# DC_IDE_Adapter.net
KiCad netlist of a schematic drawn in EAGLE
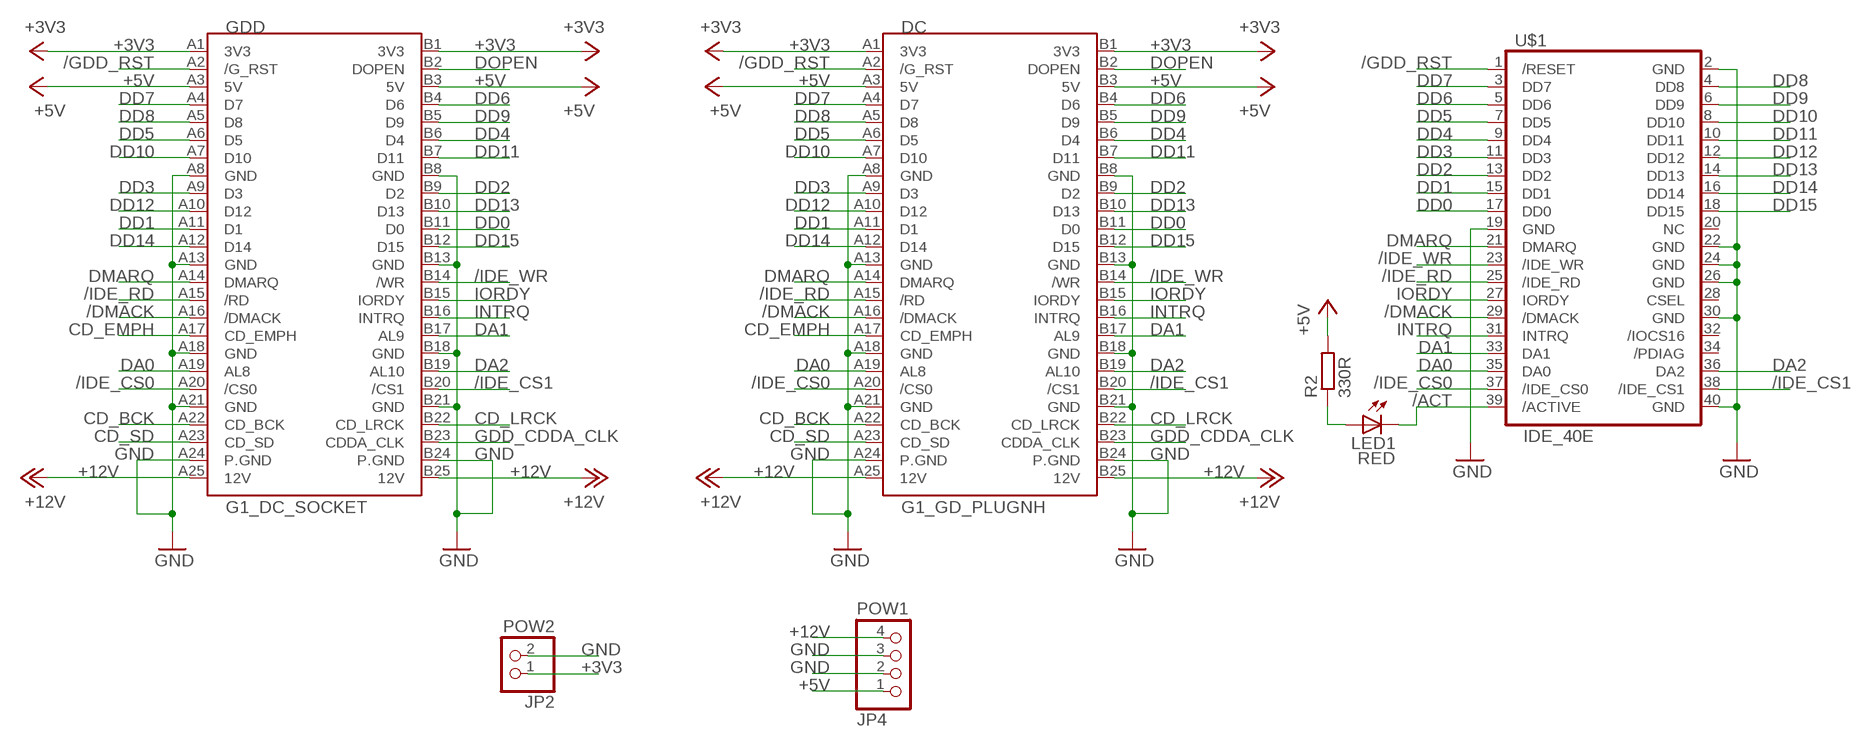
[diagram p0: schematic, sheet 1]

(export (version "E")
  (design (tool "Eeschema 10.0.6"))
  (components
    (comp (ref "DC")
      (value "G1_GD_PLUGNH")
      (footprint "eagle-import:52584-0579-NOHOLES")
      (libsource (lib "eagle-import") (part "G1_GD_PLUGNH"))
    )
    (comp (ref "GDD")
      (value "G1_DC_SOCKET")
      (footprint "eagle-import:53408-0579")
      (libsource (lib "eagle-import") (part "G1_DC_SOCKET"))
    )
    (comp (ref "JP2")
      (value "POW2")
      (footprint "eagle-import:1X02_90")
      (libsource (lib "eagle-import") (part "PINHD-1X2/90"))
    )
    (comp (ref "JP4")
      (value "POW1")
      (footprint "eagle-import:1X04_90")
      (libsource (lib "eagle-import") (part "PINHD-1X4/90"))
    )
    (comp (ref "LED1")
      (value "RED")
      (footprint "eagle-import:LED3MM")
      (libsource (lib "eagle-import") (part "LED3MM"))
    )
    (comp (ref "R2")
      (value "330R")
      (footprint "eagle-import:R0603")
      (libsource (lib "eagle-import") (part "R-EU_R0603"))
    )
    (comp (ref "U$1")
      (value "IDE_40E")
      (footprint "eagle-import:IDE_40_EDGE")
      (libsource (lib "eagle-import") (part "IDE_40E"))
    )
  )
  (nets
    (net (code "1") (name "+3V3") (class "Default")
      (node (ref "DC") (pin "A1") (pinfunction "3V3_A1") (pintype "passive"))
      (node (ref "DC") (pin "B1") (pinfunction "3V3_B1") (pintype "passive"))
      (node (ref "GDD") (pin "A1") (pinfunction "3V3_A1") (pintype "passive"))
      (node (ref "GDD") (pin "B1") (pinfunction "3V3_B1") (pintype "passive"))
      (node (ref "JP2") (pin "1") (pinfunction "1_1") (pintype "passive"))
    )
    (net (code "2") (name "+5V") (class "Default")
      (node (ref "DC") (pin "A3") (pinfunction "5V_A3") (pintype "passive"))
      (node (ref "DC") (pin "B3") (pinfunction "5V_B3") (pintype "passive"))
      (node (ref "GDD") (pin "A3") (pinfunction "5V_A3") (pintype "passive"))
      (node (ref "GDD") (pin "B3") (pinfunction "5V_B3") (pintype "passive"))
      (node (ref "JP4") (pin "1") (pinfunction "1_1") (pintype "passive"))
      (node (ref "R2") (pin "2") (pinfunction "2_2") (pintype "passive"))
    )
    (net (code "3") (name "+12V") (class "Default")
      (node (ref "DC") (pin "A25") (pinfunction "12V_A25") (pintype "passive"))
      (node (ref "DC") (pin "B25") (pinfunction "12V_B25") (pintype "passive"))
      (node (ref "GDD") (pin "A25") (pinfunction "12V_A25") (pintype "passive"))
      (node (ref "GDD") (pin "B25") (pinfunction "12V_B25") (pintype "passive"))
      (node (ref "JP4") (pin "4") (pinfunction "4_4") (pintype "passive"))
    )
    (net (code "4") (name "/CD_BCK") (class "Default")
      (node (ref "DC") (pin "A22") (pinfunction "CD_BCK_A22") (pintype "passive"))
      (node (ref "GDD") (pin "A22") (pinfunction "CD_BCK_A22") (pintype "passive"))
    )
    (net (code "5") (name "/CD_EMPH") (class "Default")
      (node (ref "DC") (pin "A17") (pinfunction "CD_EMPH_A17") (pintype "passive"))
      (node (ref "GDD") (pin "A17") (pinfunction "CD_EMPH_A17") (pintype "passive"))
    )
    (net (code "6") (name "/CD_LRCK") (class "Default")
      (node (ref "DC") (pin "B22") (pinfunction "CD_LRCK_B22") (pintype "passive"))
      (node (ref "GDD") (pin "B22") (pinfunction "CD_LRCK_B22") (pintype "passive"))
    )
    (net (code "7") (name "/CD_SD") (class "Default")
      (node (ref "DC") (pin "A23") (pinfunction "CD_SD_A23") (pintype "passive"))
      (node (ref "GDD") (pin "A23") (pinfunction "CD_SD_A23") (pintype "passive"))
    )
    (net (code "8") (name "/DA0") (class "Default")
      (node (ref "DC") (pin "A19") (pinfunction "AL8_A19") (pintype "passive"))
      (node (ref "GDD") (pin "A19") (pinfunction "AL8_A19") (pintype "passive"))
      (node (ref "U$1") (pin "35") (pinfunction "DA0_35") (pintype "input"))
    )
    (net (code "9") (name "/DA1") (class "Default")
      (node (ref "DC") (pin "B17") (pinfunction "AL9_B17") (pintype "passive"))
      (node (ref "GDD") (pin "B17") (pinfunction "AL9_B17") (pintype "passive"))
      (node (ref "U$1") (pin "33") (pinfunction "DA1_33") (pintype "input"))
    )
    (net (code "10") (name "/DA2") (class "Default")
      (node (ref "DC") (pin "B19") (pinfunction "AL10_B19") (pintype "passive"))
      (node (ref "GDD") (pin "B19") (pinfunction "AL10_B19") (pintype "passive"))
      (node (ref "U$1") (pin "36") (pinfunction "DA2_36") (pintype "input"))
    )
    (net (code "11") (name "/DD0") (class "Default")
      (node (ref "DC") (pin "B11") (pinfunction "D0_B11") (pintype "passive"))
      (node (ref "GDD") (pin "B11") (pinfunction "D0_B11") (pintype "passive"))
      (node (ref "U$1") (pin "17") (pinfunction "DD0_17") (pintype "bidirectional"))
    )
    (net (code "12") (name "/DD1") (class "Default")
      (node (ref "DC") (pin "A11") (pinfunction "D1_A11") (pintype "passive"))
      (node (ref "GDD") (pin "A11") (pinfunction "D1_A11") (pintype "passive"))
      (node (ref "U$1") (pin "15") (pinfunction "DD1_15") (pintype "bidirectional"))
    )
    (net (code "13") (name "/DD2") (class "Default")
      (node (ref "DC") (pin "B9") (pinfunction "D2_B9") (pintype "passive"))
      (node (ref "GDD") (pin "B9") (pinfunction "D2_B9") (pintype "passive"))
      (node (ref "U$1") (pin "13") (pinfunction "DD2_13") (pintype "bidirectional"))
    )
    (net (code "14") (name "/DD3") (class "Default")
      (node (ref "DC") (pin "A9") (pinfunction "D3_A9") (pintype "passive"))
      (node (ref "GDD") (pin "A9") (pinfunction "D3_A9") (pintype "passive"))
      (node (ref "U$1") (pin "11") (pinfunction "DD3_11") (pintype "bidirectional"))
    )
    (net (code "15") (name "/DD4") (class "Default")
      (node (ref "DC") (pin "B6") (pinfunction "D4_B6") (pintype "passive"))
      (node (ref "GDD") (pin "B6") (pinfunction "D4_B6") (pintype "passive"))
      (node (ref "U$1") (pin "9") (pinfunction "DD4_9") (pintype "bidirectional"))
    )
    (net (code "16") (name "/DD5") (class "Default")
      (node (ref "DC") (pin "A6") (pinfunction "D5_A6") (pintype "passive"))
      (node (ref "GDD") (pin "A6") (pinfunction "D5_A6") (pintype "passive"))
      (node (ref "U$1") (pin "7") (pinfunction "DD5_7") (pintype "bidirectional"))
    )
    (net (code "17") (name "/DD6") (class "Default")
      (node (ref "DC") (pin "B4") (pinfunction "D6_B4") (pintype "passive"))
      (node (ref "GDD") (pin "B4") (pinfunction "D6_B4") (pintype "passive"))
      (node (ref "U$1") (pin "5") (pinfunction "DD6_5") (pintype "bidirectional"))
    )
    (net (code "18") (name "/DD7") (class "Default")
      (node (ref "DC") (pin "A4") (pinfunction "D7_A4") (pintype "passive"))
      (node (ref "GDD") (pin "A4") (pinfunction "D7_A4") (pintype "passive"))
      (node (ref "U$1") (pin "3") (pinfunction "DD7_3") (pintype "bidirectional"))
    )
    (net (code "19") (name "/DD8") (class "Default")
      (node (ref "DC") (pin "A5") (pinfunction "D8_A5") (pintype "passive"))
      (node (ref "GDD") (pin "A5") (pinfunction "D8_A5") (pintype "passive"))
      (node (ref "U$1") (pin "4") (pinfunction "DD8_4") (pintype "bidirectional"))
    )
    (net (code "20") (name "/DD9") (class "Default")
      (node (ref "DC") (pin "B5") (pinfunction "D9_B5") (pintype "passive"))
      (node (ref "GDD") (pin "B5") (pinfunction "D9_B5") (pintype "passive"))
      (node (ref "U$1") (pin "6") (pinfunction "DD9_6") (pintype "bidirectional"))
    )
    (net (code "21") (name "/DD10") (class "Default")
      (node (ref "DC") (pin "A7") (pinfunction "D10_A7") (pintype "passive"))
      (node (ref "GDD") (pin "A7") (pinfunction "D10_A7") (pintype "passive"))
      (node (ref "U$1") (pin "8") (pinfunction "DD10_8") (pintype "bidirectional"))
    )
    (net (code "22") (name "/DD11") (class "Default")
      (node (ref "DC") (pin "B7") (pinfunction "D11_B7") (pintype "passive"))
      (node (ref "GDD") (pin "B7") (pinfunction "D11_B7") (pintype "passive"))
      (node (ref "U$1") (pin "10") (pinfunction "DD11_10") (pintype "bidirectional"))
    )
    (net (code "23") (name "/DD12") (class "Default")
      (node (ref "DC") (pin "A10") (pinfunction "D12_A10") (pintype "passive"))
      (node (ref "GDD") (pin "A10") (pinfunction "D12_A10") (pintype "passive"))
      (node (ref "U$1") (pin "12") (pinfunction "DD12_12") (pintype "bidirectional"))
    )
    (net (code "24") (name "/DD13") (class "Default")
      (node (ref "DC") (pin "B10") (pinfunction "D13_B10") (pintype "passive"))
      (node (ref "GDD") (pin "B10") (pinfunction "D13_B10") (pintype "passive"))
      (node (ref "U$1") (pin "14") (pinfunction "DD13_14") (pintype "bidirectional"))
    )
    (net (code "25") (name "/DD14") (class "Default")
      (node (ref "DC") (pin "A12") (pinfunction "D14_A12") (pintype "passive"))
      (node (ref "GDD") (pin "A12") (pinfunction "D14_A12") (pintype "passive"))
      (node (ref "U$1") (pin "16") (pinfunction "DD14_16") (pintype "bidirectional"))
    )
    (net (code "26") (name "/DD15") (class "Default")
      (node (ref "DC") (pin "B12") (pinfunction "D15_B12") (pintype "passive"))
      (node (ref "GDD") (pin "B12") (pinfunction "D15_B12") (pintype "passive"))
      (node (ref "U$1") (pin "18") (pinfunction "DD15_18") (pintype "bidirectional"))
    )
    (net (code "27") (name "/DMARQ") (class "Default")
      (node (ref "DC") (pin "A14") (pinfunction "DMARQ_A14") (pintype "passive"))
      (node (ref "GDD") (pin "A14") (pinfunction "DMARQ_A14") (pintype "passive"))
      (node (ref "U$1") (pin "21") (pinfunction "DMARQ_21") (pintype "output"))
    )
    (net (code "28") (name "/DOPEN") (class "Default")
      (node (ref "DC") (pin "B2") (pinfunction "DOPEN_B2") (pintype "passive"))
      (node (ref "GDD") (pin "B2") (pinfunction "DOPEN_B2") (pintype "passive"))
    )
    (net (code "29") (name "/GDD_CDDA_CLK") (class "Default")
      (node (ref "DC") (pin "B23") (pinfunction "CDDA_CLK_B23") (pintype "passive"))
      (node (ref "GDD") (pin "B23") (pinfunction "CDDA_CLK_B23") (pintype "passive"))
    )
    (net (code "30") (name "/INTRQ") (class "Default")
      (node (ref "DC") (pin "B16") (pinfunction "INTRQ_B16") (pintype "passive"))
      (node (ref "GDD") (pin "B16") (pinfunction "INTRQ_B16") (pintype "passive"))
      (node (ref "U$1") (pin "31") (pinfunction "INTRQ_31") (pintype "output"))
    )
    (net (code "31") (name "/IORDY") (class "Default")
      (node (ref "DC") (pin "B15") (pinfunction "IORDY_B15") (pintype "passive"))
      (node (ref "GDD") (pin "B15") (pinfunction "IORDY_B15") (pintype "passive"))
      (node (ref "U$1") (pin "27") (pinfunction "IORDY_27") (pintype "bidirectional"))
    )
    (net (code "32") (name "/{slash}ACT") (class "Default")
      (node (ref "LED1") (pin "K") (pinfunction "C_K") (pintype "passive"))
      (node (ref "U$1") (pin "39") (pinfunction "/ACTIVE_39") (pintype "output"))
    )
    (net (code "33") (name "/{slash}DMACK") (class "Default")
      (node (ref "DC") (pin "A16") (pinfunction "/DMACK_A16") (pintype "passive"))
      (node (ref "GDD") (pin "A16") (pinfunction "/DMACK_A16") (pintype "passive"))
      (node (ref "U$1") (pin "29") (pinfunction "/DMACK_29") (pintype "input"))
    )
    (net (code "34") (name "/{slash}GDD_RST") (class "Default")
      (node (ref "DC") (pin "A2") (pinfunction "/G_RST_A2") (pintype "passive"))
      (node (ref "GDD") (pin "A2") (pinfunction "/G_RST_A2") (pintype "passive"))
      (node (ref "U$1") (pin "1") (pinfunction "/RESET_1") (pintype "input"))
    )
    (net (code "35") (name "/{slash}IDE_CS0") (class "Default")
      (node (ref "DC") (pin "A20") (pinfunction "/CS0_A20") (pintype "passive"))
      (node (ref "GDD") (pin "A20") (pinfunction "/CS0_A20") (pintype "passive"))
      (node (ref "U$1") (pin "37") (pinfunction "/IDE_CS0_37") (pintype "input"))
    )
    (net (code "36") (name "/{slash}IDE_CS1") (class "Default")
      (node (ref "DC") (pin "B20") (pinfunction "/CS1_B20") (pintype "passive"))
      (node (ref "GDD") (pin "B20") (pinfunction "/CS1_B20") (pintype "passive"))
      (node (ref "U$1") (pin "38") (pinfunction "/IDE_CS1_38") (pintype "input"))
    )
    (net (code "37") (name "/{slash}IDE_RD") (class "Default")
      (node (ref "DC") (pin "A15") (pinfunction "/RD_A15") (pintype "passive"))
      (node (ref "GDD") (pin "A15") (pinfunction "/RD_A15") (pintype "passive"))
      (node (ref "U$1") (pin "25") (pinfunction "/IDE_RD_25") (pintype "input"))
    )
    (net (code "38") (name "/{slash}IDE_WR") (class "Default")
      (node (ref "DC") (pin "B14") (pinfunction "/WR_B14") (pintype "passive"))
      (node (ref "GDD") (pin "B14") (pinfunction "/WR_B14") (pintype "passive"))
      (node (ref "U$1") (pin "23") (pinfunction "/IDE_WR_23") (pintype "input"))
    )
    (net (code "39") (name "GND") (class "Default")
      (node (ref "DC") (pin "A13") (pinfunction "GND_A13") (pintype "passive"))
      (node (ref "DC") (pin "A18") (pinfunction "GND_A18") (pintype "passive"))
      (node (ref "DC") (pin "A21") (pinfunction "GND_A21") (pintype "passive"))
      (node (ref "DC") (pin "A24") (pinfunction "P.GND_A24") (pintype "passive"))
      (node (ref "DC") (pin "A8") (pinfunction "GND_A8") (pintype "passive"))
      (node (ref "DC") (pin "B13") (pinfunction "GND_B13") (pintype "passive"))
      (node (ref "DC") (pin "B18") (pinfunction "GND_B18") (pintype "passive"))
      (node (ref "DC") (pin "B21") (pinfunction "GND_B21") (pintype "passive"))
      (node (ref "DC") (pin "B24") (pinfunction "P.GND_B24") (pintype "passive"))
      (node (ref "DC") (pin "B8") (pinfunction "GND_B8") (pintype "passive"))
      (node (ref "GDD") (pin "A13") (pinfunction "GND_A13") (pintype "passive"))
      (node (ref "GDD") (pin "A18") (pinfunction "GND_A18") (pintype "passive"))
      (node (ref "GDD") (pin "A21") (pinfunction "GND_A21") (pintype "passive"))
      (node (ref "GDD") (pin "A24") (pinfunction "P.GND_A24") (pintype "passive"))
      (node (ref "GDD") (pin "A8") (pinfunction "GND_A8") (pintype "passive"))
      (node (ref "GDD") (pin "B13") (pinfunction "GND_B13") (pintype "passive"))
      (node (ref "GDD") (pin "B18") (pinfunction "GND_B18") (pintype "passive"))
      (node (ref "GDD") (pin "B21") (pinfunction "GND_B21") (pintype "passive"))
      (node (ref "GDD") (pin "B24") (pinfunction "P.GND_B24") (pintype "passive"))
      (node (ref "GDD") (pin "B8") (pinfunction "GND_B8") (pintype "passive"))
      (node (ref "JP2") (pin "2") (pinfunction "2_2") (pintype "passive"))
      (node (ref "JP4") (pin "2") (pinfunction "2_2") (pintype "passive"))
      (node (ref "JP4") (pin "3") (pinfunction "3_3") (pintype "passive"))
      (node (ref "U$1") (pin "19") (pinfunction "GND_19") (pintype "power_in"))
      (node (ref "U$1") (pin "2") (pinfunction "GND_2") (pintype "power_in"))
      (node (ref "U$1") (pin "22") (pinfunction "GND_22") (pintype "power_in"))
      (node (ref "U$1") (pin "24") (pinfunction "GND_24") (pintype "power_in"))
      (node (ref "U$1") (pin "26") (pinfunction "GND_26") (pintype "power_in"))
      (node (ref "U$1") (pin "30") (pinfunction "GND_30") (pintype "power_in"))
      (node (ref "U$1") (pin "40") (pinfunction "GND_40") (pintype "power_in"))
    )
    (net (code "40") (name "Net-(LED1-PadA)") (class "Default")
      (node (ref "LED1") (pin "A") (pinfunction "A_A") (pintype "passive"))
      (node (ref "R2") (pin "1") (pinfunction "1_1") (pintype "passive"))
    )
    (net (code "41") (name "unconnected-(U$1-CSEL-Pad28)") (class "Default")
      (node (ref "U$1") (pin "28") (pinfunction "CSEL_28") (pintype "bidirectional"))
    )
    (net (code "42") (name "unconnected-(U$1-NC-Pad20)") (class "Default")
      (node (ref "U$1") (pin "20") (pinfunction "NC_20") (pintype "bidirectional"))
    )
    (net (code "43") (name "unconnected-(U$1-{slash}IOCS16-Pad32)") (class "Default")
      (node (ref "U$1") (pin "32") (pinfunction "/IOCS16_32") (pintype "bidirectional"))
    )
    (net (code "44") (name "unconnected-(U$1-{slash}PDIAG-Pad34)") (class "Default")
      (node (ref "U$1") (pin "34") (pinfunction "/PDIAG_34") (pintype "bidirectional"))
    )
  )
)
